# CH32V208W-NFC-R0-1v5.net
KiCad netlist of a schematic drawn in Altium Designer
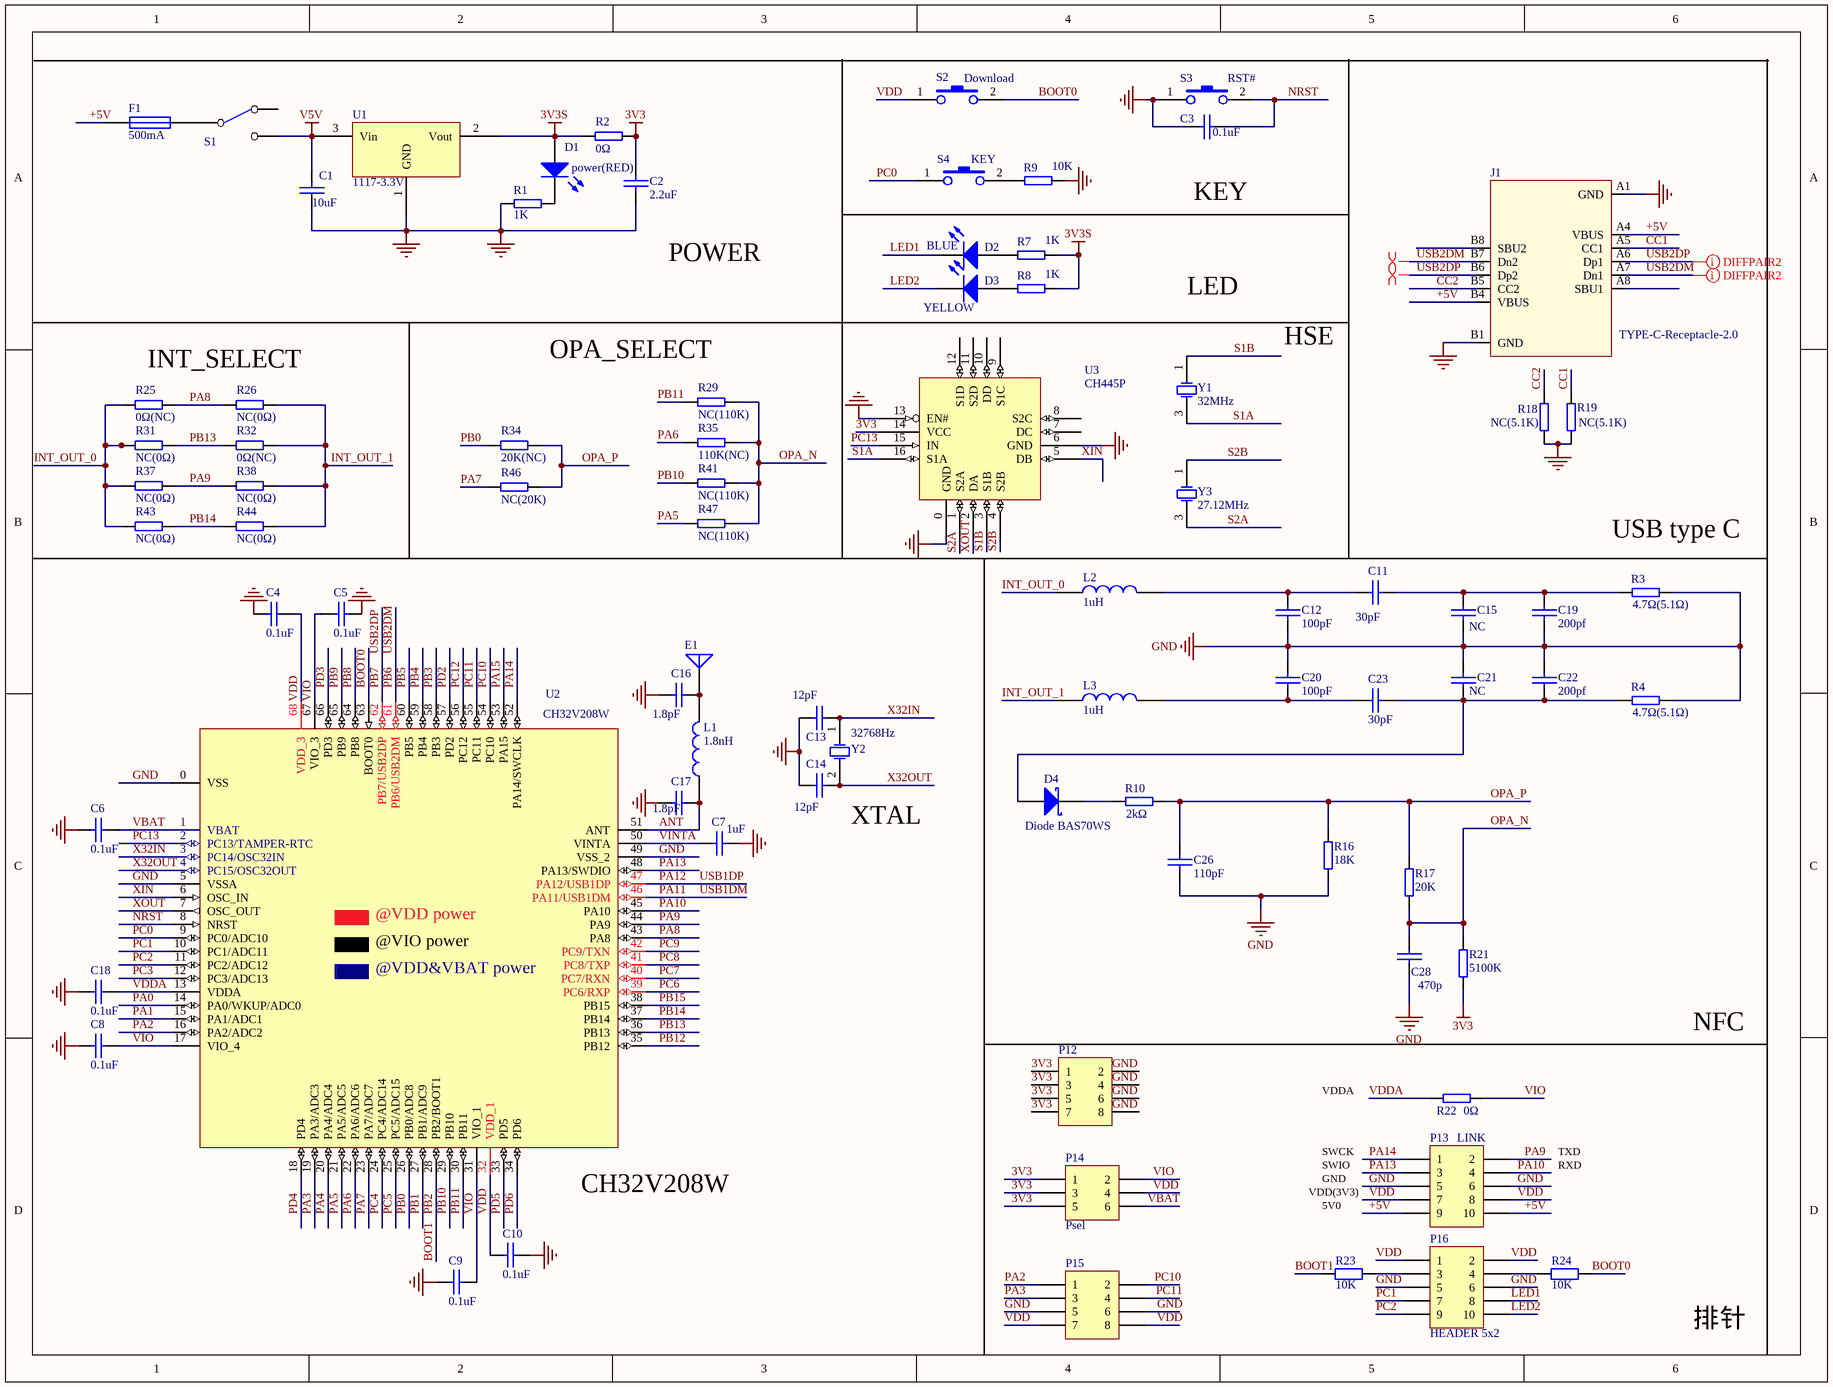
[diagram p0: CH32V208W-NFC-R0-1v5.SchDoc]

(export (version "E")
  (design (tool "Eeschema 10.0.6"))
  (components
    (comp (ref "C1")
      (value "10uF")
      (footprint "3216_C")
      (description "Capacitor")
      (libsource (lib "") (part "CAP_1"))
    )
    (comp (ref "C2")
      (value "2.2uF")
      (footprint "0603_C")
      (description "Capacitor")
      (libsource (lib "") (part "CAP_1"))
    )
    (comp (ref "C3")
      (value "0.1uF")
      (footprint "0603_C")
      (description "Capacitor")
      (libsource (lib "*") (part "CAP"))
    )
    (comp (ref "C4")
      (value "0.1uF")
      (footprint "0603_C")
      (description "Capacitor")
      (libsource (lib "*") (part "CAP"))
    )
    (comp (ref "C5")
      (value "0.1uF")
      (footprint "0603_C")
      (description "Capacitor")
      (libsource (lib "*") (part "CAP"))
    )
    (comp (ref "C6")
      (value "0.1uF")
      (footprint "0603_C")
      (description "Capacitor")
      (libsource (lib "*") (part "CAP"))
    )
    (comp (ref "C7")
      (value "1uF")
      (footprint "0603_C")
      (description "Capacitor")
      (libsource (lib "*") (part "CAP"))
    )
    (comp (ref "C8")
      (value "0.1uF")
      (footprint "0603_C")
      (description "Capacitor")
      (libsource (lib "*") (part "CAP"))
    )
    (comp (ref "C9")
      (value "0.1uF")
      (footprint "0603_C")
      (description "Capacitor")
      (libsource (lib "*") (part "CAP"))
    )
    (comp (ref "C10")
      (value "0.1uF")
      (footprint "0603_C")
      (description "Capacitor")
      (libsource (lib "*") (part "CAP"))
    )
    (comp (ref "C11")
      (value "30pF")
      (footprint "0603_C")
      (description "Capacitor")
      (libsource (lib "wch_sch_others") (part "CAP"))
    )
    (comp (ref "C12")
      (value "100pF")
      (footprint "0603_C")
      (description "Capacitor")
      (libsource (lib "wch_sch_others") (part "CAP"))
    )
    (comp (ref "C13")
      (value "12pF")
      (footprint "0603_C")
      (description "Capacitor")
      (libsource (lib "") (part "CAP_1"))
    )
    (comp (ref "C14")
      (value "12pF")
      (footprint "0603_C")
      (description "Capacitor")
      (libsource (lib "") (part "CAP_1"))
    )
    (comp (ref "C15")
      (value "NC")
      (footprint "0603_C")
      (description "Capacitor")
      (libsource (lib "wch_sch_others") (part "CAP"))
    )
    (comp (ref "C16")
      (value "1.8pF")
      (footprint "0603_C")
      (description "Capacitor")
      (libsource (lib "*") (part "CAP"))
    )
    (comp (ref "C17")
      (value "1.8pF")
      (footprint "0603_C")
      (description "Capacitor")
      (libsource (lib "*") (part "CAP"))
    )
    (comp (ref "C18")
      (value "0.1uF")
      (footprint "0603_C")
      (description "Capacitor")
      (libsource (lib "*") (part "CAP"))
    )
    (comp (ref "C19")
      (value "200pf")
      (footprint "0603_C")
      (description "Capacitor")
      (libsource (lib "wch_sch_others") (part "CAP"))
    )
    (comp (ref "C20")
      (value "100pF")
      (footprint "0603_C")
      (description "Capacitor")
      (libsource (lib "wch_sch_others") (part "CAP"))
    )
    (comp (ref "C21")
      (value "NC")
      (footprint "0603_C")
      (description "Capacitor")
      (libsource (lib "wch_sch_others") (part "CAP"))
    )
    (comp (ref "C22")
      (value "200pf")
      (footprint "0603_C")
      (description "Capacitor")
      (libsource (lib "wch_sch_others") (part "CAP"))
    )
    (comp (ref "C23")
      (value "30pF")
      (footprint "0603_C")
      (description "Capacitor")
      (libsource (lib "wch_sch_others") (part "CAP"))
    )
    (comp (ref "C26")
      (value "110pF")
      (footprint "0603_C")
      (description "Capacitor")
      (libsource (lib "wch_sch_others") (part "CAP"))
    )
    (comp (ref "C28")
      (value "470p")
      (footprint "0603_C")
      (description "Capacitor")
      (libsource (lib "wch_sch_others") (part "CAP"))
    )
    (comp (ref "D1")
      (value "power(RED)")
      (footprint "0603+")
      (description "Typical INFRARED GaAs LED")
      (fields (field (name "PUBLISHER") "Altium Limited"))
      (libsource (lib "*") (part "LED0"))
    )
    (comp (ref "D2")
      (value "BLUE")
      (footprint "0603+")
      (description "Typical INFRARED GaAs LED")
      (fields (field (name "PUBLISHER") "Altium Limited"))
      (libsource (lib "*") (part "LED0"))
    )
    (comp (ref "D3")
      (value "YELLOW")
      (footprint "0603+")
      (description "Typical INFRARED GaAs LED")
      (fields (field (name "PUBLISHER") "Altium Limited"))
      (libsource (lib "*") (part "LED0"))
    )
    (comp (ref "D4")
      (value "Diode BAS70WS")
      (footprint "3528+")
      (description "Silicon AF Schottky Diode for High-Speed Switching")
      (libsource (lib "Miscellaneous Devices") (part "Diode BAS70"))
    )
    (comp (ref "E1")
      (value "ANTENNA")
      (footprint "ANT-F-1-2.4G-1.6mmFR4")
      (description "Generic Antenna")
      (libsource (lib "wch_sch_others") (part "ANTENNA"))
    )
    (comp (ref "F1")
      (value "500mA")
      (footprint "0603")
      (description "Fuse")
      (libsource (lib "wch_sch_others") (part "FUSE1"))
    )
    (comp (ref "J1")
      (value "TYPE-C-Receptacle-2.0")
      (footprint "TYPE-C-Receptacle-2.0")
      (description "Type-C USB2.0 母座")
      (libsource (lib "Miscellaneous SCH Lib") (part "TYPE-C-Receptacle-2.0"))
    )
    (comp (ref "L1") (value "1.8nH") (footprint "0603") (libsource (lib "*") (part "INDUCTOR")))
    (comp (ref "L2") (value "1uH") (footprint "0805") (libsource (lib "*") (part "INDUCTOR")))
    (comp (ref "L3") (value "1uH") (footprint "0805") (libsource (lib "*") (part "INDUCTOR")))
    (comp (ref "P12")
      (value "Header 4X2")
      (footprint "IDC8-2.54mm")
      (description "Header, 4-Pin, Dual row")
      (fields (field (name "PUBLISHER") "Altium Limited"))
      (libsource (lib "Miscellaneous Connectors") (part "Header 4X2"))
    )
    (comp (ref "P13")
      (value "LINK")
      (footprint "IDC10-2.54mm")
      (description "Header, 5-Pin, Dual row, Right Angle")
      (fields (field (name "PUBLISHER") "Altium Limited"))
      (libsource (lib "Miscellaneous Connectors") (part "Header 5X2H"))
    )
    (comp (ref "P14")
      (value "Psel")
      (footprint "IDC6-2.54mm")
      (description "Header, 3-Pin, Dual row, Right Angle")
      (fields (field (name "PUBLISHER") "Altium Limited"))
      (libsource (lib "Miscellaneous Connectors") (part "Header 3X2H"))
    )
    (comp (ref "P15")
      (value "Header 4X2")
      (footprint "IDC8-2.54mm")
      (description "Header, 4-Pin, Dual row")
      (fields (field (name "PUBLISHER") "Altium Limited"))
      (libsource (lib "Miscellaneous Connectors") (part "Header 4X2"))
    )
    (comp (ref "P16")
      (value "HEADER 5x2")
      (footprint "MYPCB:IDC10-2.54mm")
      (description "Header, 5-Pin, Dual row")
      (libsource (lib "wch_sch_others") (part "HEADER 5x2"))
    )
    (comp (ref "R1") (value "1K") (footprint "0603") (libsource (lib "wch_sch_others") (part "RES")))
    (comp (ref "R2") (value "0Ω") (footprint "0603") (libsource (lib "wch_sch_others") (part "RES")))
    (comp (ref "R3") (value "4.7Ω(5.1Ω)") (footprint "0603") (libsource (lib "wch_sch_others") (part "RES")))
    (comp (ref "R4") (value "4.7Ω(5.1Ω)") (footprint "0603") (libsource (lib "wch_sch_others") (part "RES")))
    (comp (ref "R7") (value "1K") (footprint "0603") (libsource (lib "wch_sch_others") (part "RES")))
    (comp (ref "R8") (value "1K") (footprint "0603") (libsource (lib "wch_sch_others") (part "RES")))
    (comp (ref "R9") (value "10K") (footprint "0603") (libsource (lib "wch_sch_others") (part "RES")))
    (comp (ref "R10") (value "2kΩ") (footprint "0603") (libsource (lib "wch_sch_others") (part "RES")))
    (comp (ref "R16") (value "18K") (footprint "0603") (libsource (lib "wch_sch_others") (part "RES")))
    (comp (ref "R17") (value "20K") (footprint "0603") (libsource (lib "wch_sch_others") (part "RES")))
    (comp (ref "R18") (value "NC(5.1K)") (footprint "0603") (libsource (lib "wch_sch_others") (part "RES")))
    (comp (ref "R19") (value "NC(5.1K)") (footprint "0603") (libsource (lib "wch_sch_others") (part "RES")))
    (comp (ref "R21") (value "5100K") (footprint "0603") (libsource (lib "wch_sch_others") (part "RES")))
    (comp (ref "R22") (value "0Ω") (footprint "0603") (libsource (lib "*") (part "R")))
    (comp (ref "R23")
      (value "10K")
      (footprint "0603")
      (description "Resistor")
      (libsource (lib "Miscellaneous Devices") (part "Res2"))
    )
    (comp (ref "R24")
      (value "10K")
      (footprint "0603")
      (description "Resistor")
      (libsource (lib "Miscellaneous Devices") (part "Res2"))
    )
    (comp (ref "R25") (value "0Ω(NC)") (footprint "0603") (libsource (lib "wch_sch_others") (part "RES")))
    (comp (ref "R26") (value "NC(0Ω)") (footprint "0603") (libsource (lib "wch_sch_others") (part "RES")))
    (comp (ref "R29") (value "NC(110K)") (footprint "0603") (libsource (lib "wch_sch_others") (part "RES")))
    (comp (ref "R31") (value "NC(0Ω)") (footprint "0603") (libsource (lib "wch_sch_others") (part "RES")))
    (comp (ref "R32") (value "0Ω(NC)") (footprint "0603") (libsource (lib "wch_sch_others") (part "RES")))
    (comp (ref "R34") (value "20K(NC)") (footprint "0603") (libsource (lib "wch_sch_others") (part "RES")))
    (comp (ref "R35") (value "110K(NC)") (footprint "0603") (libsource (lib "wch_sch_others") (part "RES")))
    (comp (ref "R37") (value "NC(0Ω)") (footprint "0603") (libsource (lib "wch_sch_others") (part "RES")))
    (comp (ref "R38") (value "NC(0Ω)") (footprint "0603") (libsource (lib "wch_sch_others") (part "RES")))
    (comp (ref "R41") (value "NC(110K)") (footprint "0603") (libsource (lib "wch_sch_others") (part "RES")))
    (comp (ref "R43") (value "NC(0Ω)") (footprint "0603") (libsource (lib "wch_sch_others") (part "RES")))
    (comp (ref "R44") (value "NC(0Ω)") (footprint "0603") (libsource (lib "wch_sch_others") (part "RES")))
    (comp (ref "R46") (value "NC(20K)") (footprint "0603") (libsource (lib "wch_sch_others") (part "RES")))
    (comp (ref "R47") (value "NC(110K)") (footprint "0603") (libsource (lib "wch_sch_others") (part "RES")))
    (comp (ref "S1") (value "SW SPDT") (footprint "SW1") (libsource (lib "*") (part "SW SPDT")))
    (comp (ref "S2")
      (value "Download")
      (footprint "SMD_6.1x3.65x2.5mm-KEY")
      (libsource (lib "wch_sch_others") (part "KEY1"))
    )
    (comp (ref "S3")
      (value "RST#")
      (footprint "SMD_6.1x3.65x2.5mm-KEY")
      (libsource (lib "wch_sch_others") (part "KEY1"))
    )
    (comp (ref "S4")
      (value "KEY")
      (footprint "SMD_6.1x3.65x2.5mm-KEY")
      (libsource (lib "wch_sch_others") (part "KEY1"))
    )
    (comp (ref "U1")
      (value "1117-3.3V")
      (footprint "SOT-223")
      (libsource (lib "wch_sch_others") (part "1117-3.3V"))
    )
    (comp (ref "U2")
      (value "CH32V208W")
      (footprint "QFN68_8x8")
      (description "RISC-V BLE5.3 MCU, 10M Ethernet, 2*USB, CAN")
      (libsource (lib "CHXXX") (part "CH32V208W"))
    )
    (comp (ref "U3")
      (value "CH445P")
      (footprint "QFN16_3X3")
      (description "QPDT Low resistance mux 2:1 Analog switches with enable for 3.3V")
      (libsource (lib "CHXXX") (part "CH445P"))
    )
    (comp (ref "Y1")
      (value "32MHz")
      (footprint "XT3225")
      (description "Crystal Oscillator")
      (fields (field (name "PUBLISHER") "Altium Limited"))
      (libsource (lib "") (part "XTAL_1"))
    )
    (comp (ref "Y2")
      (value "32768Hz")
      (footprint "FC-135")
      (description "Crystal Oscillator")
      (fields (field (name "PUBLISHER") "Altium Limited"))
      (libsource (lib "*") (part "XTAL"))
    )
    (comp (ref "Y3")
      (value "27.12MHz")
      (footprint "XT3225")
      (description "Crystal Oscillator")
      (fields (field (name "PUBLISHER") "Altium Limited"))
      (libsource (lib "") (part "XTAL_1"))
    )
  )
  (nets
    (net (code "1") (name "/+5V") (class "Default")
      (node (ref "F1") (pin "1") (pinfunction "1_1") (pintype "passive"))
      (node (ref "J1") (pin "A4") (pinfunction "VBUS_A4") (pintype "passive"))
      (node (ref "J1") (pin "B4") (pinfunction "VBUS_B4") (pintype "passive"))
      (node (ref "P13") (pin "10") (pinfunction "10_10") (pintype "passive"))
      (node (ref "P13") (pin "9") (pinfunction "9_9") (pintype "passive"))
    )
    (net (code "2") (name "/ANT") (class "Default")
      (node (ref "C17") (pin "2") (pinfunction "2_2") (pintype "passive"))
      (node (ref "L1") (pin "1") (pinfunction "1_1") (pintype "passive"))
      (node (ref "U2") (pin "51") (pinfunction "ANT_51") (pintype "power_in"))
    )
    (net (code "3") (name "/BOOT0") (class "Default")
      (node (ref "R24") (pin "2") (pinfunction "2_2") (pintype "passive"))
      (node (ref "S2") (pin "2") (pinfunction "2_2") (pintype "passive"))
      (node (ref "U2") (pin "63") (pinfunction "BOOT0_63") (pintype "input"))
    )
    (net (code "4") (name "/BOOT1") (class "Default")
      (node (ref "R23") (pin "1") (pinfunction "1_1") (pintype "passive"))
      (node (ref "U2") (pin "28") (pinfunction "PB2/BOOT1_28") (pintype "bidirectional"))
    )
    (net (code "5") (name "/CC1") (class "Default")
      (node (ref "J1") (pin "A5") (pinfunction "CC1_A5") (pintype "passive"))
      (node (ref "R19") (pin "1") (pintype "passive"))
    )
    (net (code "6") (name "/CC2") (class "Default")
      (node (ref "J1") (pin "B5") (pinfunction "CC2_B5") (pintype "passive"))
      (node (ref "R18") (pin "1") (pintype "passive"))
    )
    (net (code "7") (name "/INT_OUT_0") (class "Default")
      (node (ref "L2") (pin "1") (pinfunction "1_1") (pintype "passive"))
      (node (ref "R25") (pin "2") (pintype "passive"))
      (node (ref "R31") (pin "2") (pintype "passive"))
      (node (ref "R37") (pin "2") (pintype "passive"))
      (node (ref "R43") (pin "2") (pintype "passive"))
    )
    (net (code "8") (name "/INT_OUT_1") (class "Default")
      (node (ref "L3") (pin "1") (pinfunction "1_1") (pintype "passive"))
      (node (ref "R26") (pin "1") (pintype "passive"))
      (node (ref "R32") (pin "1") (pintype "passive"))
      (node (ref "R38") (pin "1") (pintype "passive"))
      (node (ref "R44") (pin "1") (pintype "passive"))
    )
    (net (code "9") (name "/LED1") (class "Default")
      (node (ref "D2") (pin "2") (pinfunction "K_2") (pintype "passive"))
      (node (ref "P16") (pin "8") (pinfunction "8_8") (pintype "passive"))
    )
    (net (code "10") (name "/LED2") (class "Default")
      (node (ref "D3") (pin "2") (pinfunction "K_2") (pintype "passive"))
      (node (ref "P16") (pin "10") (pinfunction "10_10") (pintype "passive"))
    )
    (net (code "11") (name "/NRST") (class "Default")
      (node (ref "C3") (pin "2") (pinfunction "2_2") (pintype "passive"))
      (node (ref "S3") (pin "2") (pinfunction "2_2") (pintype "passive"))
      (node (ref "U2") (pin "8") (pinfunction "NRST_8") (pintype "input"))
    )
    (net (code "12") (name "/OPA_N") (class "Default")
      (node (ref "C28") (pin "2") (pinfunction "2_2") (pintype "passive"))
      (node (ref "R17") (pin "1") (pintype "passive"))
      (node (ref "R21") (pin "2") (pintype "passive"))
      (node (ref "R29") (pin "1") (pintype "passive"))
      (node (ref "R35") (pin "1") (pintype "passive"))
      (node (ref "R41") (pin "1") (pintype "passive"))
      (node (ref "R47") (pin "1") (pintype "passive"))
    )
    (net (code "13") (name "/OPA_P") (class "Default")
      (node (ref "C26") (pin "2") (pinfunction "2_2") (pintype "passive"))
      (node (ref "R10") (pin "2") (pintype "passive"))
      (node (ref "R16") (pin "2") (pintype "passive"))
      (node (ref "R17") (pin "2") (pintype "passive"))
      (node (ref "R34") (pin "1") (pintype "passive"))
      (node (ref "R46") (pin "1") (pintype "passive"))
    )
    (net (code "14") (name "/PA0") (class "Default")
      (node (ref "U2") (pin "14") (pinfunction "PA0/WKUP/ADC0_14") (pintype "bidirectional"))
    )
    (net (code "15") (name "/PA1") (class "Default")
      (node (ref "U2") (pin "15") (pinfunction "PA1/ADC1_15") (pintype "bidirectional"))
    )
    (net (code "16") (name "/PA2") (class "Default")
      (node (ref "P15") (pin "1") (pinfunction "1_1") (pintype "passive"))
      (node (ref "U2") (pin "16") (pinfunction "PA2/ADC2_16") (pintype "bidirectional"))
    )
    (net (code "17") (name "/PA3") (class "Default")
      (node (ref "P15") (pin "3") (pinfunction "3_3") (pintype "passive"))
      (node (ref "U2") (pin "19") (pinfunction "PA3/ADC3_19") (pintype "bidirectional"))
    )
    (net (code "18") (name "/PA4") (class "Default")
      (node (ref "U2") (pin "20") (pinfunction "PA4/ADC4_20") (pintype "bidirectional"))
    )
    (net (code "19") (name "/PA5") (class "Default")
      (node (ref "R47") (pin "2") (pintype "passive"))
      (node (ref "U2") (pin "21") (pinfunction "PA5/ADC5_21") (pintype "bidirectional"))
    )
    (net (code "20") (name "/PA6") (class "Default")
      (node (ref "R35") (pin "2") (pintype "passive"))
      (node (ref "U2") (pin "22") (pinfunction "PA6/ADC6_22") (pintype "bidirectional"))
    )
    (net (code "21") (name "/PA7") (class "Default")
      (node (ref "R46") (pin "2") (pintype "passive"))
      (node (ref "U2") (pin "23") (pinfunction "PA7/ADC7_23") (pintype "bidirectional"))
    )
    (net (code "22") (name "/PA8") (class "Default")
      (node (ref "R25") (pin "1") (pintype "passive"))
      (node (ref "R26") (pin "2") (pintype "passive"))
      (node (ref "U2") (pin "43") (pinfunction "PA8_43") (pintype "bidirectional"))
    )
    (net (code "23") (name "/PA9") (class "Default")
      (node (ref "P13") (pin "2") (pinfunction "2_2") (pintype "passive"))
      (node (ref "R37") (pin "1") (pintype "passive"))
      (node (ref "R38") (pin "2") (pintype "passive"))
      (node (ref "U2") (pin "44") (pinfunction "PA9_44") (pintype "bidirectional"))
    )
    (net (code "24") (name "/PA10") (class "Default")
      (node (ref "P13") (pin "4") (pinfunction "4_4") (pintype "passive"))
      (node (ref "U2") (pin "45") (pinfunction "PA10_45") (pintype "bidirectional"))
    )
    (net (code "25") (name "/PA11") (class "Default")
      (node (ref "U2") (pin "46") (pinfunction "PA11/USB1DM_46") (pintype "bidirectional"))
    )
    (net (code "26") (name "/PA12") (class "Default")
      (node (ref "U2") (pin "47") (pinfunction "PA12/USB1DP_47") (pintype "bidirectional"))
    )
    (net (code "27") (name "/PA13") (class "Default")
      (node (ref "P13") (pin "3") (pinfunction "3_3") (pintype "passive"))
      (node (ref "U2") (pin "48") (pinfunction "PA13/SWDIO_48") (pintype "bidirectional"))
    )
    (net (code "28") (name "/PA14") (class "Default")
      (node (ref "P13") (pin "1") (pinfunction "1_1") (pintype "passive"))
      (node (ref "U2") (pin "52") (pinfunction "PA14/SWCLK_52") (pintype "bidirectional"))
    )
    (net (code "29") (name "/PA15") (class "Default")
      (node (ref "U2") (pin "53") (pinfunction "PA15_53") (pintype "bidirectional"))
    )
    (net (code "30") (name "/PB0") (class "Default")
      (node (ref "R34") (pin "2") (pintype "passive"))
      (node (ref "U2") (pin "26") (pinfunction "PB0/ADC8_26") (pintype "bidirectional"))
    )
    (net (code "31") (name "/PB1") (class "Default")
      (node (ref "U2") (pin "27") (pinfunction "PB1/ADC9_27") (pintype "bidirectional"))
    )
    (net (code "32") (name "/PB3") (class "Default")
      (node (ref "U2") (pin "58") (pinfunction "PB3_58") (pintype "bidirectional"))
    )
    (net (code "33") (name "/PB4") (class "Default")
      (node (ref "U2") (pin "59") (pinfunction "PB4_59") (pintype "bidirectional"))
    )
    (net (code "34") (name "/PB5") (class "Default")
      (node (ref "U2") (pin "60") (pinfunction "PB5_60") (pintype "bidirectional"))
    )
    (net (code "35") (name "/PB6") (class "Default")
      (node (ref "J1") (pin "A7") (pinfunction "Dn1_A7") (pintype "passive"))
      (node (ref "J1") (pin "B7") (pinfunction "Dn2_B7") (pintype "passive"))
      (node (ref "U2") (pin "61") (pinfunction "PB6/USB2DM_61") (pintype "bidirectional"))
    )
    (net (code "36") (name "/PB7") (class "Default")
      (node (ref "J1") (pin "A6") (pinfunction "Dp1_A6") (pintype "passive"))
      (node (ref "J1") (pin "B6") (pinfunction "Dp2_B6") (pintype "passive"))
      (node (ref "U2") (pin "62") (pinfunction "PB7/USB2DP_62") (pintype "bidirectional"))
    )
    (net (code "37") (name "/PB8") (class "Default")
      (node (ref "U2") (pin "64") (pinfunction "PB8_64") (pintype "bidirectional"))
    )
    (net (code "38") (name "/PB9") (class "Default")
      (node (ref "U2") (pin "65") (pinfunction "PB9_65") (pintype "bidirectional"))
    )
    (net (code "39") (name "/PB10") (class "Default")
      (node (ref "R41") (pin "2") (pintype "passive"))
      (node (ref "U2") (pin "29") (pinfunction "PB10_29") (pintype "bidirectional"))
    )
    (net (code "40") (name "/PB11") (class "Default")
      (node (ref "R29") (pin "2") (pintype "passive"))
      (node (ref "U2") (pin "30") (pinfunction "PB11_30") (pintype "bidirectional"))
    )
    (net (code "41") (name "/PB12") (class "Default")
      (node (ref "U2") (pin "35") (pinfunction "PB12_35") (pintype "bidirectional"))
    )
    (net (code "42") (name "/PB13") (class "Default")
      (node (ref "R31") (pin "1") (pintype "passive"))
      (node (ref "R32") (pin "2") (pintype "passive"))
      (node (ref "U2") (pin "36") (pinfunction "PB13_36") (pintype "bidirectional"))
    )
    (net (code "43") (name "/PB14") (class "Default")
      (node (ref "R43") (pin "1") (pintype "passive"))
      (node (ref "R44") (pin "2") (pintype "passive"))
      (node (ref "U2") (pin "37") (pinfunction "PB14_37") (pintype "bidirectional"))
    )
    (net (code "44") (name "/PB15") (class "Default")
      (node (ref "U2") (pin "38") (pinfunction "PB15_38") (pintype "bidirectional"))
    )
    (net (code "45") (name "/PC0") (class "Default")
      (node (ref "S4") (pin "1") (pinfunction "1_1") (pintype "passive"))
      (node (ref "U2") (pin "9") (pinfunction "PC0/ADC10_9") (pintype "bidirectional"))
    )
    (net (code "46") (name "/PC1") (class "Default")
      (node (ref "P16") (pin "7") (pinfunction "7_7") (pintype "passive"))
      (node (ref "U2") (pin "10") (pinfunction "PC1/ADC11_10") (pintype "bidirectional"))
    )
    (net (code "47") (name "/PC2") (class "Default")
      (node (ref "P16") (pin "9") (pinfunction "9_9") (pintype "passive"))
      (node (ref "U2") (pin "11") (pinfunction "PC2/ADC12_11") (pintype "bidirectional"))
    )
    (net (code "48") (name "/PC3") (class "Default")
      (node (ref "U2") (pin "12") (pinfunction "PC3/ADC13_12") (pintype "bidirectional"))
    )
    (net (code "49") (name "/PC4") (class "Default")
      (node (ref "U2") (pin "24") (pinfunction "PC4/ADC14_24") (pintype "bidirectional"))
    )
    (net (code "50") (name "/PC5") (class "Default")
      (node (ref "U2") (pin "25") (pinfunction "PC5/ADC15_25") (pintype "bidirectional"))
    )
    (net (code "51") (name "/PC6") (class "Default")
      (node (ref "U2") (pin "39") (pinfunction "PC6/RXP_39") (pintype "bidirectional"))
    )
    (net (code "52") (name "/PC7") (class "Default")
      (node (ref "U2") (pin "40") (pinfunction "PC7/RXN_40") (pintype "bidirectional"))
    )
    (net (code "53") (name "/PC8") (class "Default")
      (node (ref "U2") (pin "41") (pinfunction "PC8/TXP_41") (pintype "bidirectional"))
    )
    (net (code "54") (name "/PC9") (class "Default")
      (node (ref "U2") (pin "42") (pinfunction "PC9/TXN_42") (pintype "bidirectional"))
    )
    (net (code "55") (name "/PC10") (class "Default")
      (node (ref "P15") (pin "2") (pinfunction "2_2") (pintype "passive"))
      (node (ref "U2") (pin "54") (pinfunction "PC10_54") (pintype "bidirectional"))
    )
    (net (code "56") (name "/PC11") (class "Default")
      (node (ref "P15") (pin "4") (pinfunction "4_4") (pintype "passive"))
      (node (ref "U2") (pin "55") (pinfunction "PC11_55") (pintype "bidirectional"))
    )
    (net (code "57") (name "/PC12") (class "Default")
      (node (ref "U2") (pin "56") (pinfunction "PC12_56") (pintype "bidirectional"))
    )
    (net (code "58") (name "/PC13") (class "Default")
      (node (ref "U2") (pin "2") (pinfunction "PC13/TAMPER-RTC_2") (pintype "bidirectional"))
      (node (ref "U3") (pin "15") (pinfunction "IN_15") (pintype "input"))
    )
    (net (code "59") (name "/PD2") (class "Default")
      (node (ref "U2") (pin "57") (pinfunction "PD2_57") (pintype "bidirectional"))
    )
    (net (code "60") (name "/PD3") (class "Default")
      (node (ref "U2") (pin "66") (pinfunction "PD3_66") (pintype "bidirectional"))
    )
    (net (code "61") (name "/PD4") (class "Default")
      (node (ref "U2") (pin "18") (pinfunction "PD4_18") (pintype "bidirectional"))
    )
    (net (code "62") (name "/PD5") (class "Default")
      (node (ref "U2") (pin "33") (pinfunction "PD5_33") (pintype "bidirectional"))
    )
    (net (code "63") (name "/PD6") (class "Default")
      (node (ref "U2") (pin "34") (pinfunction "PD6_34") (pintype "bidirectional"))
    )
    (net (code "64") (name "/S1A") (class "Default")
      (node (ref "U3") (pin "16") (pinfunction "S1A_16") (pintype "bidirectional"))
      (node (ref "Y1") (pin "3") (pinfunction "OSC2_3") (pintype "passive"))
    )
    (net (code "65") (name "/S1B") (class "Default")
      (node (ref "U3") (pin "3") (pinfunction "S1B_3") (pintype "bidirectional"))
      (node (ref "Y1") (pin "1") (pinfunction "OSC1_1") (pintype "passive"))
    )
    (net (code "66") (name "/S2A") (class "Default")
      (node (ref "U3") (pin "1") (pinfunction "S2A_1") (pintype "bidirectional"))
      (node (ref "Y3") (pin "3") (pinfunction "OSC2_3") (pintype "passive"))
    )
    (net (code "67") (name "/S2B") (class "Default")
      (node (ref "U3") (pin "4") (pinfunction "S2B_4") (pintype "bidirectional"))
      (node (ref "Y3") (pin "1") (pinfunction "OSC1_1") (pintype "passive"))
    )
    (net (code "68") (name "/VBAT") (class "Default")
      (node (ref "C6") (pin "1") (pinfunction "1_1") (pintype "passive"))
      (node (ref "P14") (pin "6") (pinfunction "6_6") (pintype "passive"))
      (node (ref "U2") (pin "1") (pinfunction "VBAT_1") (pintype "power_in"))
    )
    (net (code "69") (name "/VDD") (class "Default")
      (node (ref "C10") (pin "2") (pinfunction "2_2") (pintype "passive"))
      (node (ref "C4") (pin "1") (pinfunction "1_1") (pintype "passive"))
      (node (ref "P13") (pin "7") (pinfunction "7_7") (pintype "passive"))
      (node (ref "P13") (pin "8") (pinfunction "8_8") (pintype "passive"))
      (node (ref "P14") (pin "4") (pinfunction "4_4") (pintype "passive"))
      (node (ref "P15") (pin "7") (pinfunction "7_7") (pintype "passive"))
      (node (ref "P15") (pin "8") (pinfunction "8_8") (pintype "passive"))
      (node (ref "P16") (pin "1") (pinfunction "1_1") (pintype "passive"))
      (node (ref "P16") (pin "2") (pinfunction "2_2") (pintype "passive"))
      (node (ref "S2") (pin "1") (pinfunction "1_1") (pintype "passive"))
      (node (ref "U2") (pin "32") (pinfunction "VDD_1_32") (pintype "power_in"))
      (node (ref "U2") (pin "68") (pinfunction "VDD_3_68") (pintype "power_in"))
    )
    (net (code "70") (name "/VDDA") (class "Default")
      (node (ref "C18") (pin "1") (pinfunction "1_1") (pintype "passive"))
      (node (ref "R22") (pin "2") (pinfunction "2_2") (pintype "passive"))
      (node (ref "U2") (pin "13") (pinfunction "VDDA_13") (pintype "power_in"))
    )
    (net (code "71") (name "/VINTA") (class "Default")
      (node (ref "C7") (pin "1") (pinfunction "1_1") (pintype "passive"))
      (node (ref "U2") (pin "50") (pinfunction "VINTA_50") (pintype "power_in"))
    )
    (net (code "72") (name "/VIO") (class "Default")
      (node (ref "C5") (pin "2") (pinfunction "2_2") (pintype "passive"))
      (node (ref "C8") (pin "1") (pinfunction "1_1") (pintype "passive"))
      (node (ref "C9") (pin "1") (pinfunction "1_1") (pintype "passive"))
      (node (ref "P14") (pin "2") (pinfunction "2_2") (pintype "passive"))
      (node (ref "R22") (pin "1") (pinfunction "1_1") (pintype "passive"))
      (node (ref "U2") (pin "17") (pinfunction "VIO_4_17") (pintype "power_in"))
      (node (ref "U2") (pin "31") (pinfunction "VIO_1_31") (pintype "power_in"))
      (node (ref "U2") (pin "67") (pinfunction "VIO_3_67") (pintype "power_in"))
    )
    (net (code "73") (name "/X32IN") (class "Default")
      (node (ref "C13") (pin "2") (pinfunction "2_2") (pintype "passive"))
      (node (ref "U2") (pin "3") (pinfunction "PC14/OSC32IN_3") (pintype "bidirectional"))
      (node (ref "Y2") (pin "1") (pinfunction "OSC1_1") (pintype "passive"))
    )
    (net (code "74") (name "/X32OUT") (class "Default")
      (node (ref "C14") (pin "2") (pinfunction "2_2") (pintype "passive"))
      (node (ref "U2") (pin "4") (pinfunction "PC15/OSC32OUT_4") (pintype "bidirectional"))
      (node (ref "Y2") (pin "2") (pinfunction "OSC2_2") (pintype "passive"))
    )
    (net (code "75") (name "/XIN") (class "Default")
      (node (ref "U2") (pin "6") (pinfunction "OSC_IN_6") (pintype "input"))
      (node (ref "U3") (pin "5") (pinfunction "DB_5") (pintype "bidirectional"))
    )
    (net (code "76") (name "/XOUT") (class "Default")
      (node (ref "U2") (pin "7") (pinfunction "OSC_OUT_7") (pintype "output"))
      (node (ref "U3") (pin "2") (pinfunction "DA_2") (pintype "bidirectional"))
    )
    (net (code "77") (name "3V3") (class "Default")
      (node (ref "C2") (pin "1") (pinfunction "1_1") (pintype "passive"))
      (node (ref "P12") (pin "1") (pinfunction "1_1") (pintype "passive"))
      (node (ref "P12") (pin "3") (pinfunction "3_3") (pintype "passive"))
      (node (ref "P12") (pin "5") (pinfunction "5_5") (pintype "passive"))
      (node (ref "P12") (pin "7") (pinfunction "7_7") (pintype "passive"))
      (node (ref "P14") (pin "1") (pinfunction "1_1") (pintype "passive"))
      (node (ref "P14") (pin "3") (pinfunction "3_3") (pintype "passive"))
      (node (ref "P14") (pin "5") (pinfunction "5_5") (pintype "passive"))
      (node (ref "R2") (pin "1") (pintype "passive"))
      (node (ref "R21") (pin "1") (pintype "passive"))
      (node (ref "U3") (pin "14") (pinfunction "VCC_14") (pintype "power_in"))
    )
    (net (code "78") (name "3V3S") (class "Default")
      (node (ref "D1") (pin "1") (pinfunction "A_1") (pintype "passive"))
      (node (ref "R2") (pin "2") (pintype "passive"))
      (node (ref "R7") (pin "1") (pintype "passive"))
      (node (ref "R8") (pin "1") (pintype "passive"))
      (node (ref "U1") (pin "2") (pinfunction "Vout_2") (pintype "passive"))
    )
    (net (code "79") (name "GND") (class "Default")
      (node (ref "C1") (pin "2") (pinfunction "2_2") (pintype "passive"))
      (node (ref "C10") (pin "1") (pinfunction "1_1") (pintype "passive"))
      (node (ref "C12") (pin "1") (pinfunction "1_1") (pintype "passive"))
      (node (ref "C13") (pin "1") (pinfunction "1_1") (pintype "passive"))
      (node (ref "C14") (pin "1") (pinfunction "1_1") (pintype "passive"))
      (node (ref "C15") (pin "1") (pinfunction "1_1") (pintype "passive"))
      (node (ref "C16") (pin "1") (pinfunction "1_1") (pintype "passive"))
      (node (ref "C17") (pin "1") (pinfunction "1_1") (pintype "passive"))
      (node (ref "C18") (pin "2") (pinfunction "2_2") (pintype "passive"))
      (node (ref "C19") (pin "1") (pinfunction "1_1") (pintype "passive"))
      (node (ref "C2") (pin "2") (pinfunction "2_2") (pintype "passive"))
      (node (ref "C20") (pin "2") (pinfunction "2_2") (pintype "passive"))
      (node (ref "C21") (pin "2") (pinfunction "2_2") (pintype "passive"))
      (node (ref "C22") (pin "2") (pinfunction "2_2") (pintype "passive"))
      (node (ref "C26") (pin "1") (pinfunction "1_1") (pintype "passive"))
      (node (ref "C28") (pin "1") (pinfunction "1_1") (pintype "passive"))
      (node (ref "C3") (pin "1") (pinfunction "1_1") (pintype "passive"))
      (node (ref "C4") (pin "2") (pinfunction "2_2") (pintype "passive"))
      (node (ref "C5") (pin "1") (pinfunction "1_1") (pintype "passive"))
      (node (ref "C6") (pin "2") (pinfunction "2_2") (pintype "passive"))
      (node (ref "C7") (pin "2") (pinfunction "2_2") (pintype "passive"))
      (node (ref "C8") (pin "2") (pinfunction "2_2") (pintype "passive"))
      (node (ref "C9") (pin "2") (pinfunction "2_2") (pintype "passive"))
      (node (ref "J1") (pin "A1") (pinfunction "GND_A1") (pintype "passive"))
      (node (ref "J1") (pin "B1") (pinfunction "GND_B1") (pintype "passive"))
      (node (ref "P12") (pin "2") (pinfunction "2_2") (pintype "passive"))
      (node (ref "P12") (pin "4") (pinfunction "4_4") (pintype "passive"))
      (node (ref "P12") (pin "6") (pinfunction "6_6") (pintype "passive"))
      (node (ref "P12") (pin "8") (pinfunction "8_8") (pintype "passive"))
      (node (ref "P13") (pin "5") (pinfunction "5_5") (pintype "passive"))
      (node (ref "P13") (pin "6") (pinfunction "6_6") (pintype "passive"))
      (node (ref "P15") (pin "5") (pinfunction "5_5") (pintype "passive"))
      (node (ref "P15") (pin "6") (pinfunction "6_6") (pintype "passive"))
      (node (ref "P16") (pin "5") (pinfunction "5_5") (pintype "passive"))
      (node (ref "P16") (pin "6") (pinfunction "6_6") (pintype "passive"))
      (node (ref "R1") (pin "1") (pintype "passive"))
      (node (ref "R16") (pin "1") (pintype "passive"))
      (node (ref "R18") (pin "2") (pintype "passive"))
      (node (ref "R19") (pin "2") (pintype "passive"))
      (node (ref "R3") (pin "2") (pintype "passive"))
      (node (ref "R4") (pin "2") (pintype "passive"))
      (node (ref "R9") (pin "1") (pintype "passive"))
      (node (ref "S3") (pin "1") (pinfunction "1_1") (pintype "passive"))
      (node (ref "U1") (pin "1") (pinfunction "GND_1") (pintype "passive"))
      (node (ref "U2") (pin "0") (pinfunction "VSS_0") (pintype "power_in"))
      (node (ref "U2") (pin "49") (pinfunction "VSS_2_49") (pintype "power_in"))
      (node (ref "U2") (pin "5") (pinfunction "VSSA_5") (pintype "power_in"))
      (node (ref "U3") (pin "0") (pinfunction "GND_0") (pintype "power_in"))
      (node (ref "U3") (pin "13") (pinfunction "EN#_13") (pintype "input"))
      (node (ref "U3") (pin "6") (pinfunction "GND_6") (pintype "power_in"))
    )
    (net (code "80") (name "Net-(C11-Pad1)") (class "Default")
      (node (ref "C11") (pin "1") (pinfunction "1_1") (pintype "passive"))
      (node (ref "C12") (pin "2") (pinfunction "2_2") (pintype "passive"))
      (node (ref "L2") (pin "2") (pinfunction "2_2") (pintype "passive"))
    )
    (net (code "81") (name "Net-(C11-Pad2)") (class "Default")
      (node (ref "C11") (pin "2") (pinfunction "2_2") (pintype "passive"))
      (node (ref "C15") (pin "2") (pinfunction "2_2") (pintype "passive"))
      (node (ref "C19") (pin "2") (pinfunction "2_2") (pintype "passive"))
      (node (ref "R3") (pin "1") (pintype "passive"))
    )
    (net (code "82") (name "Net-(C20-Pad1)") (class "Default")
      (node (ref "C20") (pin "1") (pinfunction "1_1") (pintype "passive"))
      (node (ref "C23") (pin "1") (pinfunction "1_1") (pintype "passive"))
      (node (ref "L3") (pin "2") (pinfunction "2_2") (pintype "passive"))
    )
    (net (code "83") (name "Net-(D1-K)") (class "Default")
      (node (ref "D1") (pin "2") (pinfunction "K_2") (pintype "passive"))
      (node (ref "R1") (pin "2") (pintype "passive"))
    )
    (net (code "84") (name "Net-(D2-A)") (class "Default")
      (node (ref "D2") (pin "1") (pinfunction "A_1") (pintype "passive"))
      (node (ref "R7") (pin "2") (pintype "passive"))
    )
    (net (code "85") (name "Net-(D3-A)") (class "Default")
      (node (ref "D3") (pin "1") (pinfunction "A_1") (pintype "passive"))
      (node (ref "R8") (pin "2") (pintype "passive"))
    )
    (net (code "86") (name "Net-(D4-A)") (class "Default")
      (node (ref "C21") (pin "1") (pinfunction "1_1") (pintype "passive"))
      (node (ref "C22") (pin "1") (pinfunction "1_1") (pintype "passive"))
      (node (ref "C23") (pin "2") (pinfunction "2_2") (pintype "passive"))
      (node (ref "D4") (pin "1") (pinfunction "A_1") (pintype "passive"))
      (node (ref "R4") (pin "1") (pintype "passive"))
    )
    (net (code "87") (name "Net-(D4-K)") (class "Default")
      (node (ref "D4") (pin "2") (pinfunction "K_2") (pintype "passive"))
      (node (ref "R10") (pin "1") (pintype "passive"))
    )
    (net (code "88") (name "Net-(E1-A)") (class "Default")
      (node (ref "C16") (pin "2") (pinfunction "2_2") (pintype "passive"))
      (node (ref "E1") (pin "1") (pinfunction "A_1") (pintype "passive"))
      (node (ref "L1") (pin "2") (pinfunction "2_2") (pintype "passive"))
    )
    (net (code "89") (name "Net-(P16-Pad3)") (class "Default")
      (node (ref "P16") (pin "3") (pinfunction "3_3") (pintype "passive"))
      (node (ref "R23") (pin "2") (pinfunction "2_2") (pintype "passive"))
    )
    (net (code "90") (name "Net-(P16-Pad4)") (class "Default")
      (node (ref "P16") (pin "4") (pinfunction "4_4") (pintype "passive"))
      (node (ref "R24") (pin "1") (pinfunction "1_1") (pintype "passive"))
    )
    (net (code "91") (name "Net-(R9-Pad2)") (class "Default")
      (node (ref "R9") (pin "2") (pintype "passive"))
      (node (ref "S4") (pin "2") (pinfunction "2_2") (pintype "passive"))
    )
    (net (code "92") (name "Net-(S1-COMMON)") (class "Default")
      (node (ref "F1") (pin "2") (pinfunction "2_2") (pintype "passive"))
      (node (ref "S1") (pin "1") (pinfunction "COMMON_1") (pintype "passive"))
    )
    (net (code "93") (name "V5V") (class "Default")
      (node (ref "C1") (pin "1") (pinfunction "1_1") (pintype "passive"))
      (node (ref "S1") (pin "2") (pinfunction "NC_2") (pintype "passive"))
      (node (ref "U1") (pin "3") (pinfunction "Vin_3") (pintype "passive"))
    )
    (net (code "94") (name "unconnected-(J1-SBU1-PadA8)") (class "Default")
      (node (ref "J1") (pin "A8") (pinfunction "SBU1_A8") (pintype "passive"))
    )
    (net (code "95") (name "unconnected-(J1-SBU2-PadB8)") (class "Default")
      (node (ref "J1") (pin "B8") (pinfunction "SBU2_B8") (pintype "passive"))
    )
    (net (code "96") (name "unconnected-(S1-NO-Pad3)") (class "Default")
      (node (ref "S1") (pin "3") (pinfunction "NO_3") (pintype "passive"))
    )
    (net (code "97") (name "unconnected-(U3-DC-Pad7)") (class "Default")
      (node (ref "U3") (pin "7") (pinfunction "DC_7") (pintype "bidirectional"))
    )
    (net (code "98") (name "unconnected-(U3-DD-Pad10)") (class "Default")
      (node (ref "U3") (pin "10") (pinfunction "DD_10") (pintype "bidirectional"))
    )
    (net (code "99") (name "unconnected-(U3-S1C-Pad9)") (class "Default")
      (node (ref "U3") (pin "9") (pinfunction "S1C_9") (pintype "bidirectional"))
    )
    (net (code "100") (name "unconnected-(U3-S1D-Pad12)") (class "Default")
      (node (ref "U3") (pin "12") (pinfunction "S1D_12") (pintype "bidirectional"))
    )
    (net (code "101") (name "unconnected-(U3-S2C-Pad8)") (class "Default")
      (node (ref "U3") (pin "8") (pinfunction "S2C_8") (pintype "bidirectional"))
    )
    (net (code "102") (name "unconnected-(U3-S2D-Pad11)") (class "Default")
      (node (ref "U3") (pin "11") (pinfunction "S2D_11") (pintype "bidirectional"))
    )
  )
)
